# 5V-and-3V3-ldo.net
KiCad netlist of a schematic drawn in Altium Designer
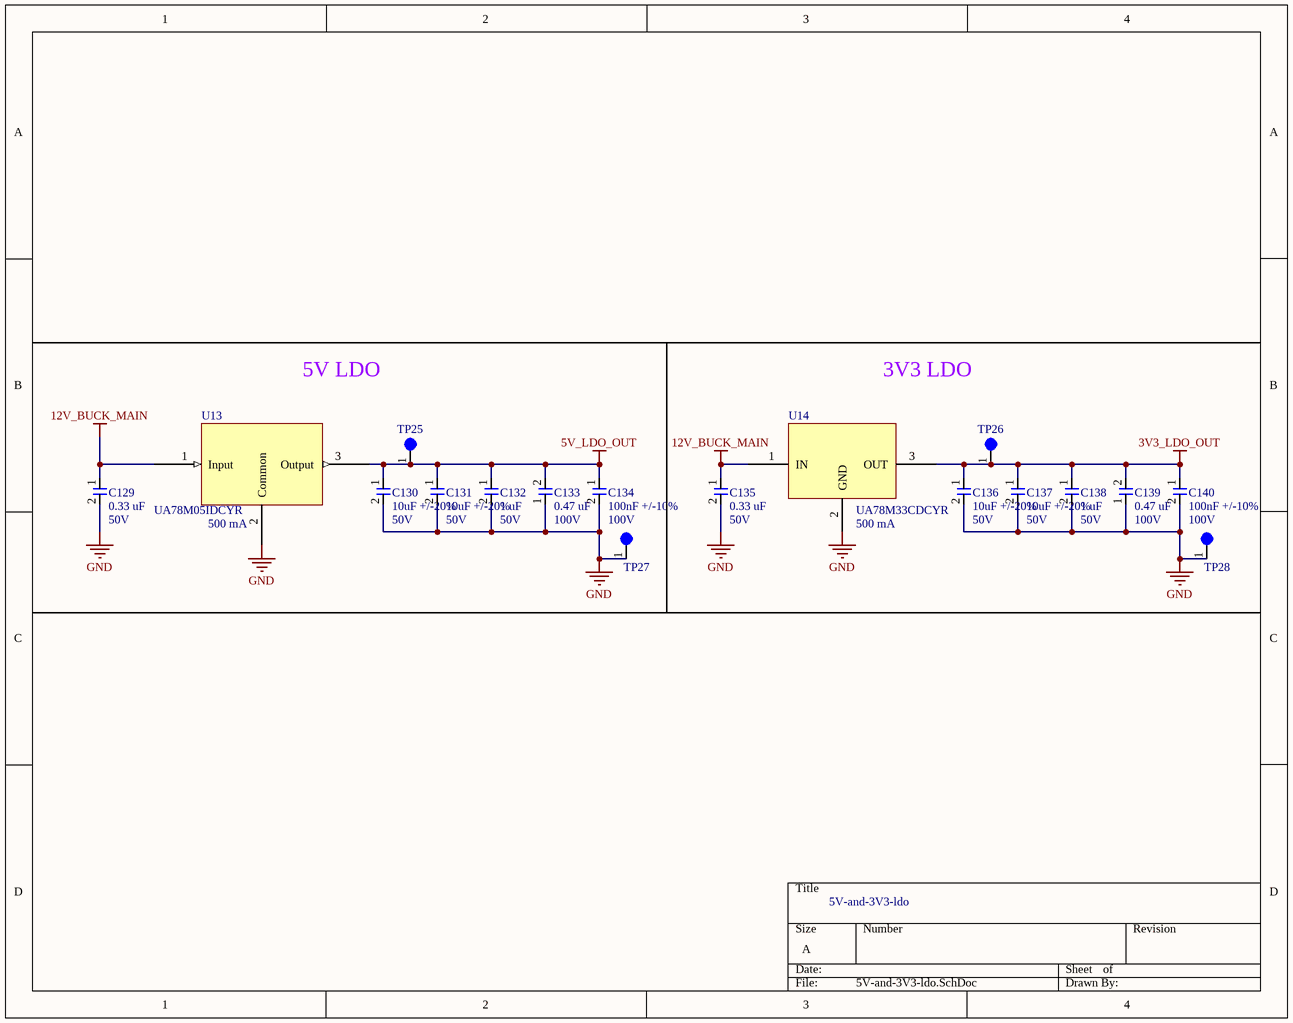
[diagram p0: 5V-and-3V3-ldo.SchDoc]

(export (version "E")
  (design (tool "Eeschema 10.0.6"))
  (components
    (comp (ref "C129")
      (value "CGA3E3X7R1H334K080AB")
      (footprint "CAP-0603")
      (description "0.33 µF ±10% 50V Ceramic Capacitor X7R 0603 (1608 Metric)")
      (fields
        (field (name "MANUFACTURER") "TDK Corporation")
        (field (name "TOLERANCE") "+/- 10%")
        (field (name "CAPACITANCE") "0.33 uF")
        (field (name "VOLTAGE") "50V")
      )
      (libsource (lib "MasterLib") (part "CAP-0.33uF-0001"))
    )
    (comp (ref "C130")
      (value "CL31B106KBHNNNE")
      (footprint "CAP-1206")
      (description "10 µF ±10% 50V Ceramic Capacitor X7R 1206 (3216 Metric)")
      (fields
        (field (name "MANUFACTURER") "Samsung Electro-Mechanics")
        (field (name "CAPACITANCE") "10uF +/-20%")
        (field (name "VOLTAGE RATING") "50V")
      )
      (libsource (lib "MasterLib") (part "CAP-10U-0001"))
    )
    (comp (ref "C131")
      (value "CL31B106KBHNNNE")
      (footprint "CAP-1206")
      (description "10 µF ±10% 50V Ceramic Capacitor X7R 1206 (3216 Metric)")
      (fields
        (field (name "MANUFACTURER") "Samsung Electro-Mechanics")
        (field (name "CAPACITANCE") "10uF +/-20%")
        (field (name "VOLTAGE RATING") "50V")
      )
      (libsource (lib "MasterLib") (part "CAP-10U-0001"))
    )
    (comp (ref "C132")
      (value "UMK107AB7105KA-T")
      (footprint "CAP-0603")
      (description "1 µF ±10% 50V Ceramic Capacitor X7R 0603 (1608 Metric)")
      (fields (field (name "CAPACITANCE") "1 uF") (field (name "VOLTAGE") "50V"))
      (libsource (lib "MasterLib") (part "CAP-1U-0002"))
    )
    (comp (ref "C133")
      (value "KAM21KR72A474KL")
      (footprint "CAP-0805")
      (description "0.47 µF ±10% 100V Ceramic Capacitor X7R 0805 (2012 Metric)")
      (fields
        (field (name "TOLERANCE") "+/- 10%")
        (field (name "CAPACITANCE") "0.47 uF")
        (field (name "VOLTAGE") "100V")
      )
      (libsource (lib "MasterLib") (part "CAP-0.47U-0001"))
    )
    (comp (ref "C134")
      (value "CC0603KRX7R0BB104")
      (footprint "CAP-0603")
      (description "CAP CER 0.1UF 100V X7R 0603")
      (fields
        (field (name "MANUFACTURER") "YAGEO")
        (field (name "CAPACITANCE") "100nF +/-10%")
        (field (name "VOLTAGE RATING") "100V")
      )
      (libsource (lib "MasterLib") (part "CAP-100N-0001"))
    )
    (comp (ref "C135")
      (value "CGA3E3X7R1H334K080AB")
      (footprint "CAP-0603")
      (description "0.33 µF ±10% 50V Ceramic Capacitor X7R 0603 (1608 Metric)")
      (fields
        (field (name "MANUFACTURER") "TDK Corporation")
        (field (name "TOLERANCE") "+/- 10%")
        (field (name "CAPACITANCE") "0.33 uF")
        (field (name "VOLTAGE") "50V")
      )
      (libsource (lib "MasterLib") (part "CAP-0.33uF-0001"))
    )
    (comp (ref "C136")
      (value "CL31B106KBHNNNE")
      (footprint "CAP-1206")
      (description "10 µF ±10% 50V Ceramic Capacitor X7R 1206 (3216 Metric)")
      (fields
        (field (name "MANUFACTURER") "Samsung Electro-Mechanics")
        (field (name "CAPACITANCE") "10uF +/-20%")
        (field (name "VOLTAGE RATING") "50V")
      )
      (libsource (lib "MasterLib") (part "CAP-10U-0001"))
    )
    (comp (ref "C137")
      (value "CL31B106KBHNNNE")
      (footprint "CAP-1206")
      (description "10 µF ±10% 50V Ceramic Capacitor X7R 1206 (3216 Metric)")
      (fields
        (field (name "MANUFACTURER") "Samsung Electro-Mechanics")
        (field (name "CAPACITANCE") "10uF +/-20%")
        (field (name "VOLTAGE RATING") "50V")
      )
      (libsource (lib "MasterLib") (part "CAP-10U-0001"))
    )
    (comp (ref "C138")
      (value "UMK107AB7105KA-T")
      (footprint "CAP-0603")
      (description "1 µF ±10% 50V Ceramic Capacitor X7R 0603 (1608 Metric)")
      (fields (field (name "CAPACITANCE") "1 uF") (field (name "VOLTAGE") "50V"))
      (libsource (lib "MasterLib") (part "CAP-1U-0002"))
    )
    (comp (ref "C139")
      (value "KAM21KR72A474KL")
      (footprint "CAP-0805")
      (description "0.47 µF ±10% 100V Ceramic Capacitor X7R 0805 (2012 Metric)")
      (fields
        (field (name "TOLERANCE") "+/- 10%")
        (field (name "CAPACITANCE") "0.47 uF")
        (field (name "VOLTAGE") "100V")
      )
      (libsource (lib "MasterLib") (part "CAP-0.47U-0001"))
    )
    (comp (ref "C140")
      (value "CC0603KRX7R0BB104")
      (footprint "CAP-0603")
      (description "CAP CER 0.1UF 100V X7R 0603")
      (fields
        (field (name "MANUFACTURER") "YAGEO")
        (field (name "CAPACITANCE") "100nF +/-10%")
        (field (name "VOLTAGE RATING") "100V")
      )
      (libsource (lib "MasterLib") (part "CAP-100N-0001"))
    )
    (comp (ref "TP25")
      (value "5003")
      (footprint "TEST-POINT-0001")
      (description "Oranange PC Test Point, Miniature Phoisphor Bronze Silver Plating Through Hole Mounting Type")
      (libsource (lib "MasterLib") (part "TEST-POINT-0001"))
    )
    (comp (ref "TP26")
      (value "5003")
      (footprint "TEST-POINT-0001")
      (description "Oranange PC Test Point, Miniature Phoisphor Bronze Silver Plating Through Hole Mounting Type")
      (libsource (lib "MasterLib") (part "TEST-POINT-0001"))
    )
    (comp (ref "TP27")
      (value "5003")
      (footprint "TEST-POINT-0001")
      (description "Oranange PC Test Point, Miniature Phoisphor Bronze Silver Plating Through Hole Mounting Type")
      (libsource (lib "MasterLib") (part "TEST-POINT-0001"))
    )
    (comp (ref "TP28")
      (value "5003")
      (footprint "TEST-POINT-0001")
      (description "Oranange PC Test Point, Miniature Phoisphor Bronze Silver Plating Through Hole Mounting Type")
      (libsource (lib "MasterLib") (part "TEST-POINT-0001"))
    )
    (comp (ref "U13")
      (value "UA78M05IDCYR")
      (footprint "IC-SOT-223-4")
      (description "Linear Voltage Regulator IC Positive Fixed 1 Output 500mA SOT-223-4")
      (fields (field (name "MANUFACTURER") "Texas Instruments") (field (name "CURRENT") "500 mA"))
      (libsource (lib "MasterLib") (part "IC-LDO-5V-0003"))
    )
    (comp (ref "U14")
      (value "UA78M33CDCYR")
      (footprint "IC-SOT-223-4")
      (description "Linear Voltage Regulator IC Positive Fixed 1 Output 500mA SOT-223-4")
      (fields (field (name "CURRENT") "500 mA"))
      (libsource (lib "MasterLib") (part "IC-LDO-3.3V-0002"))
    )
  )
  (nets
    (net (code "1") (name "3V3_LDO_OUT") (class "Default")
      (node (ref "C136") (pin "1") (pinfunction "1_1") (pintype "passive"))
      (node (ref "C137") (pin "1") (pinfunction "1_1") (pintype "passive"))
      (node (ref "C138") (pin "1") (pinfunction "1_1") (pintype "passive"))
      (node (ref "C139") (pin "2") (pinfunction "2_2") (pintype "passive"))
      (node (ref "C140") (pin "1") (pinfunction "1_1") (pintype "passive"))
      (node (ref "TP26") (pin "1") (pinfunction "0_1") (pintype "passive"))
      (node (ref "U14") (pin "3") (pinfunction "OUT_3") (pintype "power_in"))
    )
    (net (code "2") (name "5V_LDO_OUT") (class "Default")
      (node (ref "C130") (pin "1") (pinfunction "1_1") (pintype "passive"))
      (node (ref "C131") (pin "1") (pinfunction "1_1") (pintype "passive"))
      (node (ref "C132") (pin "1") (pinfunction "1_1") (pintype "passive"))
      (node (ref "C133") (pin "2") (pinfunction "2_2") (pintype "passive"))
      (node (ref "C134") (pin "1") (pinfunction "1_1") (pintype "passive"))
      (node (ref "TP25") (pin "1") (pinfunction "0_1") (pintype "passive"))
      (node (ref "U13") (pin "3") (pinfunction "Output_3") (pintype "output"))
    )
    (net (code "3") (name "12V_BUCK_MAIN") (class "Default")
      (node (ref "C129") (pin "1") (pinfunction "1_1") (pintype "passive"))
      (node (ref "C135") (pin "1") (pinfunction "1_1") (pintype "passive"))
      (node (ref "U13") (pin "1") (pinfunction "Input_1") (pintype "input"))
      (node (ref "U14") (pin "1") (pinfunction "IN_1") (pintype "power_in"))
    )
    (net (code "4") (name "GND") (class "Default")
      (node (ref "C129") (pin "2") (pinfunction "2_2") (pintype "passive"))
      (node (ref "C130") (pin "2") (pinfunction "2_2") (pintype "passive"))
      (node (ref "C131") (pin "2") (pinfunction "2_2") (pintype "passive"))
      (node (ref "C132") (pin "2") (pinfunction "2_2") (pintype "passive"))
      (node (ref "C133") (pin "1") (pinfunction "1_1") (pintype "passive"))
      (node (ref "C134") (pin "2") (pinfunction "2_2") (pintype "passive"))
      (node (ref "C135") (pin "2") (pinfunction "2_2") (pintype "passive"))
      (node (ref "C136") (pin "2") (pinfunction "2_2") (pintype "passive"))
      (node (ref "C137") (pin "2") (pinfunction "2_2") (pintype "passive"))
      (node (ref "C138") (pin "2") (pinfunction "2_2") (pintype "passive"))
      (node (ref "C139") (pin "1") (pinfunction "1_1") (pintype "passive"))
      (node (ref "C140") (pin "2") (pinfunction "2_2") (pintype "passive"))
      (node (ref "TP27") (pin "1") (pinfunction "0_1") (pintype "passive"))
      (node (ref "TP28") (pin "1") (pinfunction "0_1") (pintype "passive"))
      (node (ref "U13") (pin "2") (pinfunction "Common_2") (pintype "power_in"))
      (node (ref "U14") (pin "2") (pinfunction "GND_2") (pintype "power_in"))
    )
  )
)
